# VDC.net
KiCad netlist of a schematic drawn in EAGLE
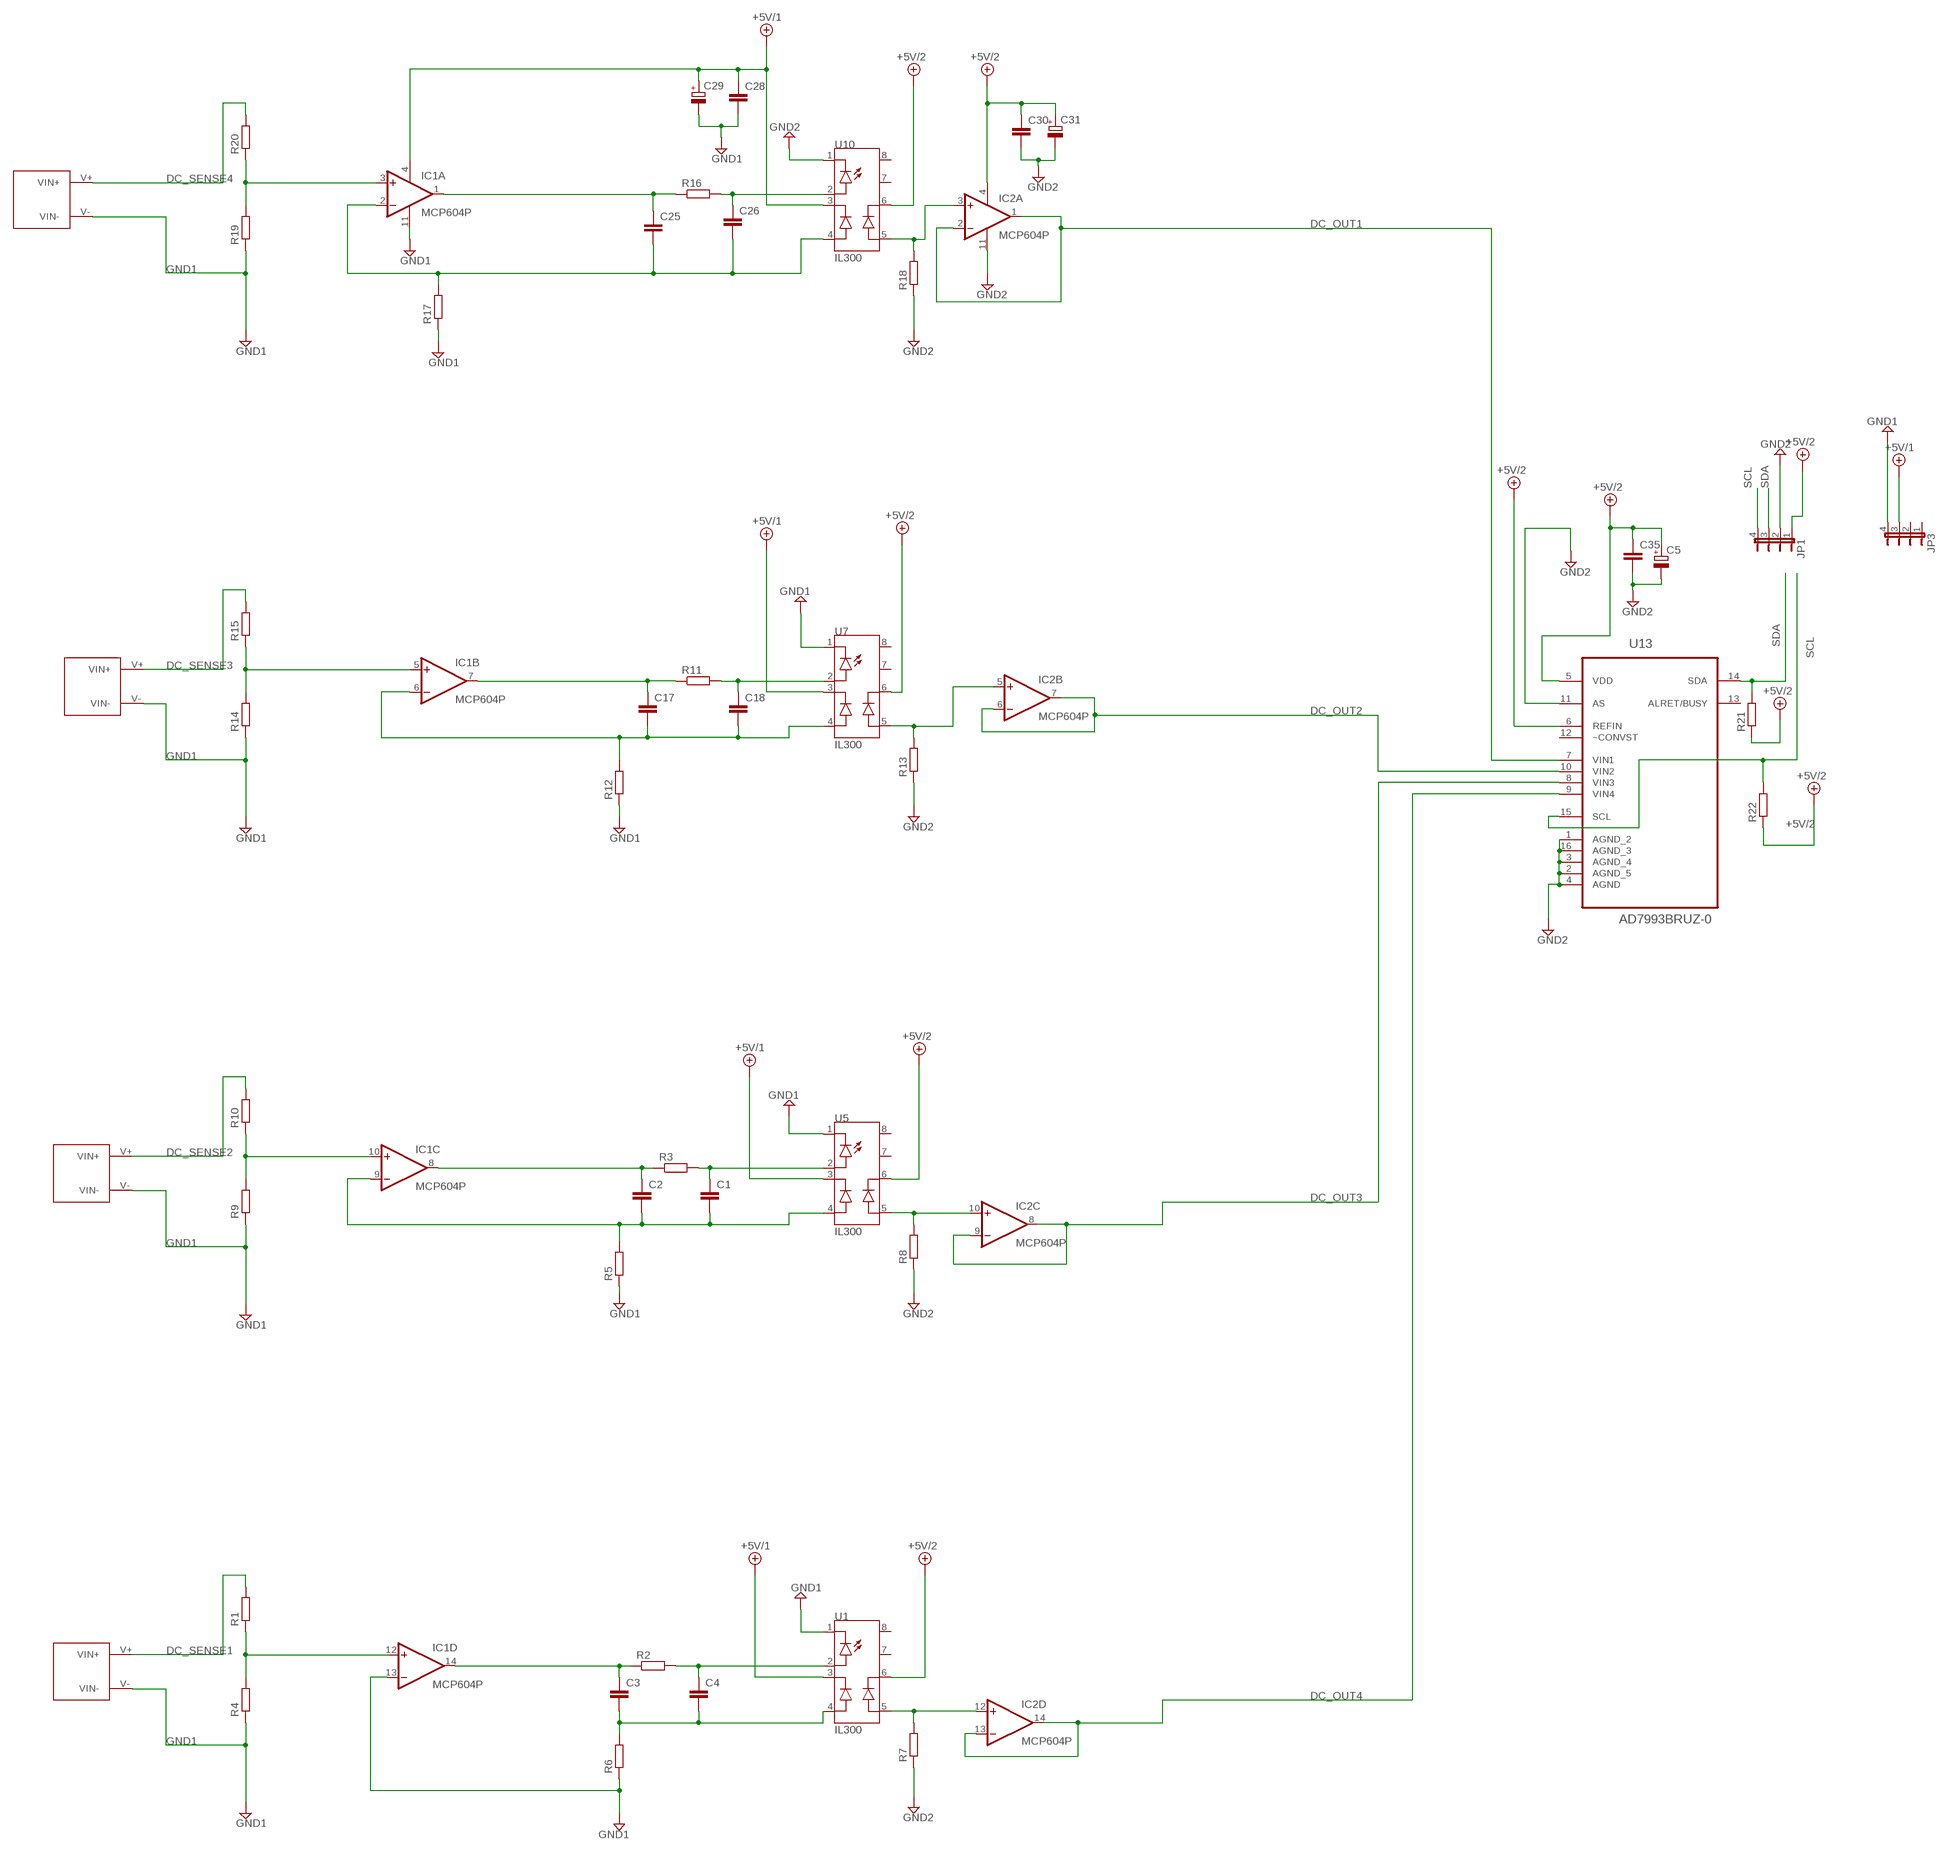
[diagram p0: schematic, sheet 1]

(export (version "E")
  (design (tool "Eeschema 10.0.6"))
  (components
    (comp (ref "C1")
      (value "C-EU025-040X050")
      (footprint "eagle-import:C025-040X050")
      (libsource (lib "eagle-import") (part "C-EU025-040X050"))
    )
    (comp (ref "C2")
      (value "C-EU025-040X050")
      (footprint "eagle-import:C025-040X050")
      (libsource (lib "eagle-import") (part "C-EU025-040X050"))
    )
    (comp (ref "C3")
      (value "C-EU025-040X050")
      (footprint "eagle-import:C025-040X050")
      (libsource (lib "eagle-import") (part "C-EU025-040X050"))
    )
    (comp (ref "C4")
      (value "C-EU025-040X050")
      (footprint "eagle-import:C025-040X050")
      (libsource (lib "eagle-import") (part "C-EU025-040X050"))
    )
    (comp (ref "C5")
      (value "CPOL-EUE2-4")
      (footprint "eagle-import:E2-4")
      (libsource (lib "eagle-import") (part "CPOL-EUE2-4"))
    )
    (comp (ref "C17")
      (value "C-EU025-040X050")
      (footprint "eagle-import:C025-040X050")
      (libsource (lib "eagle-import") (part "C-EU025-040X050"))
    )
    (comp (ref "C18")
      (value "C-EU025-040X050")
      (footprint "eagle-import:C025-040X050")
      (libsource (lib "eagle-import") (part "C-EU025-040X050"))
    )
    (comp (ref "C25")
      (value "C-EU025-040X050")
      (footprint "eagle-import:C025-040X050")
      (libsource (lib "eagle-import") (part "C-EU025-040X050"))
    )
    (comp (ref "C26")
      (value "C-EU025-040X050")
      (footprint "eagle-import:C025-040X050")
      (libsource (lib "eagle-import") (part "C-EU025-040X050"))
    )
    (comp (ref "C28")
      (value "C-EU025-040X050")
      (footprint "eagle-import:C025-040X050")
      (libsource (lib "eagle-import") (part "C-EU025-040X050"))
    )
    (comp (ref "C29")
      (value "CPOL-EUE2-5")
      (footprint "eagle-import:E2-5")
      (libsource (lib "eagle-import") (part "CPOL-EUE2-5"))
    )
    (comp (ref "C30")
      (value "C-EU025-040X050")
      (footprint "eagle-import:C025-040X050")
      (libsource (lib "eagle-import") (part "C-EU025-040X050"))
    )
    (comp (ref "C31")
      (value "CPOL-EUE2-5")
      (footprint "eagle-import:E2-5")
      (libsource (lib "eagle-import") (part "CPOL-EUE2-5"))
    )
    (comp (ref "C35")
      (value "C-EU025-025X050")
      (footprint "eagle-import:C025-025X050")
      (libsource (lib "eagle-import") (part "C-EU025-025X050"))
    )
    (comp (ref "IC1")
      (value "MCP604P")
      (footprint "eagle-import:DIL14")
      (libsource (lib "eagle-import") (part "MCP604P"))
    )
    (comp (ref "IC2")
      (value "MCP604P")
      (footprint "eagle-import:DIL14")
      (libsource (lib "eagle-import") (part "MCP604P"))
    )
    (comp (ref "JP1")
      (value "JP4E")
      (footprint "eagle-import:JP4")
      (libsource (lib "eagle-import") (part "JP4E"))
    )
    (comp (ref "JP3")
      (value "JP4E")
      (footprint "eagle-import:JP4")
      (libsource (lib "eagle-import") (part "JP4E"))
    )
    (comp (ref "R1")
      (value "R-EU_0207/10")
      (footprint "eagle-import:0207_10")
      (libsource (lib "eagle-import") (part "R-EU_0207/10"))
    )
    (comp (ref "R2")
      (value "R-EU_0207/10")
      (footprint "eagle-import:0207_10")
      (libsource (lib "eagle-import") (part "R-EU_0207/10"))
    )
    (comp (ref "R3")
      (value "R-EU_0207/10")
      (footprint "eagle-import:0207_10")
      (libsource (lib "eagle-import") (part "R-EU_0207/10"))
    )
    (comp (ref "R4")
      (value "R-EU_0207/10")
      (footprint "eagle-import:0207_10")
      (libsource (lib "eagle-import") (part "R-EU_0207/10"))
    )
    (comp (ref "R5")
      (value "R-EU_0207/10")
      (footprint "eagle-import:0207_10")
      (libsource (lib "eagle-import") (part "R-EU_0207/10"))
    )
    (comp (ref "R6")
      (value "R-EU_0207/10")
      (footprint "eagle-import:0207_10")
      (libsource (lib "eagle-import") (part "R-EU_0207/10"))
    )
    (comp (ref "R7")
      (value "R-EU_0207/10")
      (footprint "eagle-import:0207_10")
      (libsource (lib "eagle-import") (part "R-EU_0207/10"))
    )
    (comp (ref "R8")
      (value "R-EU_0207/10")
      (footprint "eagle-import:0207_10")
      (libsource (lib "eagle-import") (part "R-EU_0207/10"))
    )
    (comp (ref "R9")
      (value "R-EU_0207/10")
      (footprint "eagle-import:0207_10")
      (libsource (lib "eagle-import") (part "R-EU_0207/10"))
    )
    (comp (ref "R10")
      (value "R-EU_0207/10")
      (footprint "eagle-import:0207_10")
      (libsource (lib "eagle-import") (part "R-EU_0207/10"))
    )
    (comp (ref "R11")
      (value "R-EU_0207/10")
      (footprint "eagle-import:0207_10")
      (libsource (lib "eagle-import") (part "R-EU_0207/10"))
    )
    (comp (ref "R12")
      (value "R-EU_0207/10")
      (footprint "eagle-import:0207_10")
      (libsource (lib "eagle-import") (part "R-EU_0207/10"))
    )
    (comp (ref "R13")
      (value "R-EU_0207/10")
      (footprint "eagle-import:0207_10")
      (libsource (lib "eagle-import") (part "R-EU_0207/10"))
    )
    (comp (ref "R14")
      (value "R-EU_0207/10")
      (footprint "eagle-import:0207_10")
      (libsource (lib "eagle-import") (part "R-EU_0207/10"))
    )
    (comp (ref "R15")
      (value "R-EU_0207/10")
      (footprint "eagle-import:0207_10")
      (libsource (lib "eagle-import") (part "R-EU_0207/10"))
    )
    (comp (ref "R16")
      (value "R-EU_0207/10")
      (footprint "eagle-import:0207_10")
      (libsource (lib "eagle-import") (part "R-EU_0207/10"))
    )
    (comp (ref "R17")
      (value "R-EU_0207/10")
      (footprint "eagle-import:0207_10")
      (libsource (lib "eagle-import") (part "R-EU_0207/10"))
    )
    (comp (ref "R18")
      (value "R-EU_0207/10")
      (footprint "eagle-import:0207_10")
      (libsource (lib "eagle-import") (part "R-EU_0207/10"))
    )
    (comp (ref "R19")
      (value "R-EU_0207/10")
      (footprint "eagle-import:0207_10")
      (libsource (lib "eagle-import") (part "R-EU_0207/10"))
    )
    (comp (ref "R20")
      (value "R-EU_0207/10")
      (footprint "eagle-import:0207_10")
      (libsource (lib "eagle-import") (part "R-EU_0207/10"))
    )
    (comp (ref "R21")
      (value "R-EU_0207/10")
      (footprint "eagle-import:0207_10")
      (libsource (lib "eagle-import") (part "R-EU_0207/10"))
    )
    (comp (ref "R22")
      (value "R-EU_0207/10")
      (footprint "eagle-import:0207_10")
      (libsource (lib "eagle-import") (part "R-EU_0207/10"))
    )
    (comp (ref "U$5")
      (value "INPUT_VOLTAGE_CONNECTOR")
      (footprint "eagle-import:INPUT_VOLTAGE_CONNECTOR")
      (libsource (lib "eagle-import") (part "INPUT_VOLTAGE_CONNECTOR"))
    )
    (comp (ref "U$6")
      (value "INPUT_VOLTAGE_CONNECTOR")
      (footprint "eagle-import:INPUT_VOLTAGE_CONNECTOR")
      (libsource (lib "eagle-import") (part "INPUT_VOLTAGE_CONNECTOR"))
    )
    (comp (ref "U$7")
      (value "INPUT_VOLTAGE_CONNECTOR")
      (footprint "eagle-import:INPUT_VOLTAGE_CONNECTOR")
      (libsource (lib "eagle-import") (part "INPUT_VOLTAGE_CONNECTOR"))
    )
    (comp (ref "U$8")
      (value "INPUT_VOLTAGE_CONNECTOR")
      (footprint "eagle-import:INPUT_VOLTAGE_CONNECTOR")
      (libsource (lib "eagle-import") (part "INPUT_VOLTAGE_CONNECTOR"))
    )
    (comp (ref "U1")
      (value "IL300")
      (footprint "eagle-import:DIL08")
      (libsource (lib "eagle-import") (part "IL300"))
    )
    (comp (ref "U5")
      (value "IL300")
      (footprint "eagle-import:DIL08")
      (libsource (lib "eagle-import") (part "IL300"))
    )
    (comp (ref "U7")
      (value "IL300")
      (footprint "eagle-import:DIL08")
      (libsource (lib "eagle-import") (part "IL300"))
    )
    (comp (ref "U10")
      (value "IL300")
      (footprint "eagle-import:DIL08")
      (libsource (lib "eagle-import") (part "IL300"))
    )
    (comp (ref "U13")
      (value "AD7993BRUZ-0")
      (footprint "eagle-import:SOP65P640X120-16N")
      (libsource (lib "eagle-import") (part "AD7993BRUZ-0"))
    )
  )
  (nets
    (net (code "1") (name "+5V{slash}1") (class "Default")
      (node (ref "C28") (pin "1") (pinfunction "1_1") (pintype "passive"))
      (node (ref "C29") (pin "+") (pinfunction "+_+") (pintype "passive"))
      (node (ref "IC1") (pin "4") (pinfunction "V+_4") (pintype "power_in"))
      (node (ref "JP3") (pin "3") (pinfunction "3_3") (pintype "passive"))
      (node (ref "U1") (pin "3") (pinfunction "C_FB_3") (pintype "passive"))
      (node (ref "U10") (pin "3") (pinfunction "C_FB_3") (pintype "passive"))
      (node (ref "U5") (pin "3") (pinfunction "C_FB_3") (pintype "passive"))
      (node (ref "U7") (pin "3") (pinfunction "C_FB_3") (pintype "passive"))
    )
    (net (code "2") (name "+5V{slash}2") (class "Default")
      (node (ref "C30") (pin "1") (pinfunction "1_1") (pintype "passive"))
      (node (ref "C31") (pin "+") (pinfunction "+_+") (pintype "passive"))
      (node (ref "C35") (pin "1") (pinfunction "1_1") (pintype "passive"))
      (node (ref "C5") (pin "+") (pinfunction "+_+") (pintype "passive"))
      (node (ref "IC2") (pin "4") (pinfunction "V+_4") (pintype "power_in"))
      (node (ref "JP1") (pin "1") (pinfunction "1_1") (pintype "passive"))
      (node (ref "R21") (pin "1") (pinfunction "1_1") (pintype "passive"))
      (node (ref "R22") (pin "1") (pinfunction "1_1") (pintype "passive"))
      (node (ref "U1") (pin "6") (pinfunction "C_OUT_6") (pintype "passive"))
      (node (ref "U10") (pin "6") (pinfunction "C_OUT_6") (pintype "passive"))
      (node (ref "U13") (pin "5") (pinfunction "VDD_5") (pintype "power_in"))
      (node (ref "U13") (pin "6") (pinfunction "REFIN_6") (pintype "input"))
      (node (ref "U5") (pin "6") (pinfunction "C_OUT_6") (pintype "passive"))
      (node (ref "U7") (pin "6") (pinfunction "C_OUT_6") (pintype "passive"))
    )
    (net (code "3") (name "/DC_OUT1") (class "Default")
      (node (ref "IC2") (pin "1") (pinfunction "OUT_1") (pintype "output"))
      (node (ref "IC2") (pin "2") (pinfunction "-IN_2") (pintype "input"))
      (node (ref "U13") (pin "7") (pinfunction "VIN1_7") (pintype "input"))
    )
    (net (code "4") (name "/DC_OUT2") (class "Default")
      (node (ref "IC2") (pin "6") (pinfunction "-IN_6") (pintype "input"))
      (node (ref "IC2") (pin "7") (pinfunction "OUT_7") (pintype "output"))
      (node (ref "U13") (pin "10") (pinfunction "VIN2_10") (pintype "input"))
    )
    (net (code "5") (name "/DC_OUT3") (class "Default")
      (node (ref "IC2") (pin "8") (pinfunction "OUT_8") (pintype "output"))
      (node (ref "IC2") (pin "9") (pinfunction "-IN_9") (pintype "input"))
      (node (ref "U13") (pin "8") (pinfunction "VIN3_8") (pintype "input"))
    )
    (net (code "6") (name "/DC_OUT4") (class "Default")
      (node (ref "IC2") (pin "13") (pinfunction "-IN_13") (pintype "input"))
      (node (ref "IC2") (pin "14") (pinfunction "OUT_14") (pintype "output"))
      (node (ref "U13") (pin "9") (pinfunction "VIN4_9") (pintype "input"))
    )
    (net (code "7") (name "/DC_SENSE1") (class "Default")
      (node (ref "R1") (pin "2") (pinfunction "2_2") (pintype "passive"))
      (node (ref "U$8") (pin "V+") (pinfunction "VIN+_V+") (pintype "bidirectional"))
    )
    (net (code "8") (name "/DC_SENSE2") (class "Default")
      (node (ref "R10") (pin "2") (pinfunction "2_2") (pintype "passive"))
      (node (ref "U$7") (pin "V+") (pinfunction "VIN+_V+") (pintype "bidirectional"))
    )
    (net (code "9") (name "/DC_SENSE3") (class "Default")
      (node (ref "R15") (pin "2") (pinfunction "2_2") (pintype "passive"))
      (node (ref "U$6") (pin "V+") (pinfunction "VIN+_V+") (pintype "bidirectional"))
    )
    (net (code "10") (name "/DC_SENSE4") (class "Default")
      (node (ref "R20") (pin "2") (pinfunction "2_2") (pintype "passive"))
      (node (ref "U$5") (pin "V+") (pinfunction "VIN+_V+") (pintype "bidirectional"))
    )
    (net (code "11") (name "/SCL") (class "Default")
      (node (ref "JP1") (pin "4") (pinfunction "4_4") (pintype "passive"))
      (node (ref "R22") (pin "2") (pinfunction "2_2") (pintype "passive"))
      (node (ref "U13") (pin "15") (pinfunction "SCL_15") (pintype "input"))
    )
    (net (code "12") (name "/SDA") (class "Default")
      (node (ref "JP1") (pin "3") (pinfunction "3_3") (pintype "passive"))
      (node (ref "R21") (pin "2") (pinfunction "2_2") (pintype "passive"))
      (node (ref "U13") (pin "14") (pinfunction "SDA_14") (pintype "bidirectional"))
    )
    (net (code "13") (name "GND1") (class "Default")
      (node (ref "C28") (pin "2") (pinfunction "2_2") (pintype "passive"))
      (node (ref "C29") (pin "-") (pinfunction "-_-") (pintype "passive"))
      (node (ref "IC1") (pin "11") (pinfunction "V-_11") (pintype "power_in"))
      (node (ref "IC1") (pin "13") (pinfunction "-IN_13") (pintype "input"))
      (node (ref "JP3") (pin "4") (pinfunction "4_4") (pintype "passive"))
      (node (ref "R12") (pin "1") (pinfunction "1_1") (pintype "passive"))
      (node (ref "R14") (pin "1") (pinfunction "1_1") (pintype "passive"))
      (node (ref "R17") (pin "1") (pinfunction "1_1") (pintype "passive"))
      (node (ref "R19") (pin "1") (pinfunction "1_1") (pintype "passive"))
      (node (ref "R4") (pin "1") (pinfunction "1_1") (pintype "passive"))
      (node (ref "R5") (pin "1") (pinfunction "1_1") (pintype "passive"))
      (node (ref "R6") (pin "1") (pinfunction "1_1") (pintype "passive"))
      (node (ref "R9") (pin "1") (pinfunction "1_1") (pintype "passive"))
      (node (ref "U$5") (pin "V-") (pinfunction "VIN-_V-") (pintype "bidirectional"))
      (node (ref "U$6") (pin "V-") (pinfunction "VIN-_V-") (pintype "bidirectional"))
      (node (ref "U$7") (pin "V-") (pinfunction "VIN-_V-") (pintype "bidirectional"))
      (node (ref "U$8") (pin "V-") (pinfunction "VIN-_V-") (pintype "bidirectional"))
      (node (ref "U1") (pin "1") (pinfunction "C_LED_1") (pintype "passive"))
      (node (ref "U5") (pin "1") (pinfunction "C_LED_1") (pintype "passive"))
      (node (ref "U7") (pin "1") (pinfunction "C_LED_1") (pintype "passive"))
    )
    (net (code "14") (name "GND2") (class "Default")
      (node (ref "C30") (pin "2") (pinfunction "2_2") (pintype "passive"))
      (node (ref "C31") (pin "-") (pinfunction "-_-") (pintype "passive"))
      (node (ref "C35") (pin "2") (pinfunction "2_2") (pintype "passive"))
      (node (ref "C5") (pin "-") (pinfunction "-_-") (pintype "passive"))
      (node (ref "IC2") (pin "11") (pinfunction "V-_11") (pintype "power_in"))
      (node (ref "JP1") (pin "2") (pinfunction "2_2") (pintype "passive"))
      (node (ref "R13") (pin "1") (pinfunction "1_1") (pintype "passive"))
      (node (ref "R18") (pin "1") (pinfunction "1_1") (pintype "passive"))
      (node (ref "R7") (pin "1") (pinfunction "1_1") (pintype "passive"))
      (node (ref "R8") (pin "1") (pinfunction "1_1") (pintype "passive"))
      (node (ref "U10") (pin "1") (pinfunction "C_LED_1") (pintype "passive"))
      (node (ref "U13") (pin "1") (pinfunction "AGND_2_1") (pintype "passive"))
      (node (ref "U13") (pin "11") (pinfunction "AS_11") (pintype "input"))
      (node (ref "U13") (pin "16") (pinfunction "AGND_3_16") (pintype "passive"))
      (node (ref "U13") (pin "2") (pinfunction "AGND_5_2") (pintype "passive"))
      (node (ref "U13") (pin "3") (pinfunction "AGND_4_3") (pintype "passive"))
      (node (ref "U13") (pin "4") (pinfunction "AGND_4") (pintype "passive"))
    )
    (net (code "15") (name "Net-(IC1A-+IN)") (class "Default")
      (node (ref "IC1") (pin "3") (pinfunction "+IN_3") (pintype "input"))
      (node (ref "R19") (pin "2") (pinfunction "2_2") (pintype "passive"))
      (node (ref "R20") (pin "1") (pinfunction "1_1") (pintype "passive"))
    )
    (net (code "16") (name "Net-(IC1A--IN)") (class "Default")
      (node (ref "C25") (pin "2") (pinfunction "2_2") (pintype "passive"))
      (node (ref "C26") (pin "2") (pinfunction "2_2") (pintype "passive"))
      (node (ref "IC1") (pin "2") (pinfunction "-IN_2") (pintype "input"))
      (node (ref "R17") (pin "2") (pinfunction "2_2") (pintype "passive"))
      (node (ref "U10") (pin "4") (pinfunction "A_FB_4") (pintype "passive"))
    )
    (net (code "17") (name "Net-(IC1A-OUT)") (class "Default")
      (node (ref "C25") (pin "1") (pinfunction "1_1") (pintype "passive"))
      (node (ref "IC1") (pin "1") (pinfunction "OUT_1") (pintype "output"))
      (node (ref "R16") (pin "1") (pinfunction "1_1") (pintype "passive"))
    )
    (net (code "18") (name "Net-(IC1B-+IN)") (class "Default")
      (node (ref "IC1") (pin "5") (pinfunction "+IN_5") (pintype "input"))
      (node (ref "R14") (pin "2") (pinfunction "2_2") (pintype "passive"))
      (node (ref "R15") (pin "1") (pinfunction "1_1") (pintype "passive"))
    )
    (net (code "19") (name "Net-(IC1B--IN)") (class "Default")
      (node (ref "C17") (pin "2") (pinfunction "2_2") (pintype "passive"))
      (node (ref "C18") (pin "2") (pinfunction "2_2") (pintype "passive"))
      (node (ref "IC1") (pin "6") (pinfunction "-IN_6") (pintype "input"))
      (node (ref "R12") (pin "2") (pinfunction "2_2") (pintype "passive"))
      (node (ref "U7") (pin "4") (pinfunction "A_FB_4") (pintype "passive"))
    )
    (net (code "20") (name "Net-(IC1B-OUT)") (class "Default")
      (node (ref "C17") (pin "1") (pinfunction "1_1") (pintype "passive"))
      (node (ref "IC1") (pin "7") (pinfunction "OUT_7") (pintype "output"))
      (node (ref "R11") (pin "1") (pinfunction "1_1") (pintype "passive"))
    )
    (net (code "21") (name "Net-(IC1C-+IN)") (class "Default")
      (node (ref "IC1") (pin "10") (pinfunction "+IN_10") (pintype "input"))
      (node (ref "R10") (pin "1") (pinfunction "1_1") (pintype "passive"))
      (node (ref "R9") (pin "2") (pinfunction "2_2") (pintype "passive"))
    )
    (net (code "22") (name "Net-(IC1C--IN)") (class "Default")
      (node (ref "C1") (pin "2") (pinfunction "2_2") (pintype "passive"))
      (node (ref "C2") (pin "2") (pinfunction "2_2") (pintype "passive"))
      (node (ref "IC1") (pin "9") (pinfunction "-IN_9") (pintype "input"))
      (node (ref "R5") (pin "2") (pinfunction "2_2") (pintype "passive"))
      (node (ref "U5") (pin "4") (pinfunction "A_FB_4") (pintype "passive"))
    )
    (net (code "23") (name "Net-(IC1C-OUT)") (class "Default")
      (node (ref "C2") (pin "1") (pinfunction "1_1") (pintype "passive"))
      (node (ref "IC1") (pin "8") (pinfunction "OUT_8") (pintype "output"))
      (node (ref "R3") (pin "1") (pinfunction "1_1") (pintype "passive"))
    )
    (net (code "24") (name "Net-(IC1D-+IN)") (class "Default")
      (node (ref "IC1") (pin "12") (pinfunction "+IN_12") (pintype "input"))
      (node (ref "R1") (pin "1") (pinfunction "1_1") (pintype "passive"))
      (node (ref "R4") (pin "2") (pinfunction "2_2") (pintype "passive"))
    )
    (net (code "25") (name "Net-(IC1D-OUT)") (class "Default")
      (node (ref "C3") (pin "1") (pinfunction "1_1") (pintype "passive"))
      (node (ref "IC1") (pin "14") (pinfunction "OUT_14") (pintype "output"))
      (node (ref "R2") (pin "1") (pinfunction "1_1") (pintype "passive"))
    )
    (net (code "26") (name "Net-(IC2A-+IN)") (class "Default")
      (node (ref "IC2") (pin "3") (pinfunction "+IN_3") (pintype "input"))
      (node (ref "R18") (pin "2") (pinfunction "2_2") (pintype "passive"))
      (node (ref "U10") (pin "5") (pinfunction "A_OUT_5") (pintype "passive"))
    )
    (net (code "27") (name "Net-(IC2B-+IN)") (class "Default")
      (node (ref "IC2") (pin "5") (pinfunction "+IN_5") (pintype "input"))
      (node (ref "R13") (pin "2") (pinfunction "2_2") (pintype "passive"))
      (node (ref "U7") (pin "5") (pinfunction "A_OUT_5") (pintype "passive"))
    )
    (net (code "28") (name "Net-(IC2C-+IN)") (class "Default")
      (node (ref "IC2") (pin "10") (pinfunction "+IN_10") (pintype "input"))
      (node (ref "R8") (pin "2") (pinfunction "2_2") (pintype "passive"))
      (node (ref "U5") (pin "5") (pinfunction "A_OUT_5") (pintype "passive"))
    )
    (net (code "29") (name "Net-(IC2D-+IN)") (class "Default")
      (node (ref "IC2") (pin "12") (pinfunction "+IN_12") (pintype "input"))
      (node (ref "R7") (pin "2") (pinfunction "2_2") (pintype "passive"))
      (node (ref "U1") (pin "5") (pinfunction "A_OUT_5") (pintype "passive"))
    )
    (net (code "30") (name "Net-(U1-A_FB)") (class "Default")
      (node (ref "C3") (pin "2") (pinfunction "2_2") (pintype "passive"))
      (node (ref "C4") (pin "2") (pinfunction "2_2") (pintype "passive"))
      (node (ref "R6") (pin "2") (pinfunction "2_2") (pintype "passive"))
      (node (ref "U1") (pin "4") (pinfunction "A_FB_4") (pintype "passive"))
    )
    (net (code "31") (name "Net-(U1-A_LED)") (class "Default")
      (node (ref "C4") (pin "1") (pinfunction "1_1") (pintype "passive"))
      (node (ref "R2") (pin "2") (pinfunction "2_2") (pintype "passive"))
      (node (ref "U1") (pin "2") (pinfunction "A_LED_2") (pintype "passive"))
    )
    (net (code "32") (name "Net-(U5-A_LED)") (class "Default")
      (node (ref "C1") (pin "1") (pinfunction "1_1") (pintype "passive"))
      (node (ref "R3") (pin "2") (pinfunction "2_2") (pintype "passive"))
      (node (ref "U5") (pin "2") (pinfunction "A_LED_2") (pintype "passive"))
    )
    (net (code "33") (name "Net-(U7-A_LED)") (class "Default")
      (node (ref "C18") (pin "1") (pinfunction "1_1") (pintype "passive"))
      (node (ref "R11") (pin "2") (pinfunction "2_2") (pintype "passive"))
      (node (ref "U7") (pin "2") (pinfunction "A_LED_2") (pintype "passive"))
    )
    (net (code "34") (name "Net-(U10-A_LED)") (class "Default")
      (node (ref "C26") (pin "1") (pinfunction "1_1") (pintype "passive"))
      (node (ref "R16") (pin "2") (pinfunction "2_2") (pintype "passive"))
      (node (ref "U10") (pin "2") (pinfunction "A_LED_2") (pintype "passive"))
    )
    (net (code "35") (name "unconnected-(JP3-Pad1)") (class "Default")
      (node (ref "JP3") (pin "1") (pinfunction "1_1") (pintype "passive"))
    )
    (net (code "36") (name "unconnected-(JP3-Pad2)") (class "Default")
      (node (ref "JP3") (pin "2") (pinfunction "2_2") (pintype "passive"))
    )
    (net (code "37") (name "unconnected-(U1-PIN7-Pad7)") (class "Default")
      (node (ref "U1") (pin "7") (pinfunction "PIN7_7") (pintype "no_connect"))
    )
    (net (code "38") (name "unconnected-(U1-PIN8-Pad8)") (class "Default")
      (node (ref "U1") (pin "8") (pinfunction "PIN8_8") (pintype "no_connect"))
    )
    (net (code "39") (name "unconnected-(U5-PIN7-Pad7)") (class "Default")
      (node (ref "U5") (pin "7") (pinfunction "PIN7_7") (pintype "no_connect"))
    )
    (net (code "40") (name "unconnected-(U5-PIN8-Pad8)") (class "Default")
      (node (ref "U5") (pin "8") (pinfunction "PIN8_8") (pintype "no_connect"))
    )
    (net (code "41") (name "unconnected-(U7-PIN7-Pad7)") (class "Default")
      (node (ref "U7") (pin "7") (pinfunction "PIN7_7") (pintype "no_connect"))
    )
    (net (code "42") (name "unconnected-(U7-PIN8-Pad8)") (class "Default")
      (node (ref "U7") (pin "8") (pinfunction "PIN8_8") (pintype "no_connect"))
    )
    (net (code "43") (name "unconnected-(U10-PIN7-Pad7)") (class "Default")
      (node (ref "U10") (pin "7") (pinfunction "PIN7_7") (pintype "no_connect"))
    )
    (net (code "44") (name "unconnected-(U10-PIN8-Pad8)") (class "Default")
      (node (ref "U10") (pin "8") (pinfunction "PIN8_8") (pintype "no_connect"))
    )
    (net (code "45") (name "unconnected-(U13-ALRET{slash}BUSY-Pad13)") (class "Default")
      (node (ref "U13") (pin "13") (pinfunction "ALRET/BUSY_13") (pintype "output"))
    )
    (net (code "46") (name "unconnected-(U13-~{CONVST}-Pad12)") (class "Default")
      (node (ref "U13") (pin "12") (pinfunction "~{CONVST}_12") (pintype "input"))
    )
  )
)
